# Combined_final.net
KiCad netlist of a schematic drawn in EAGLE
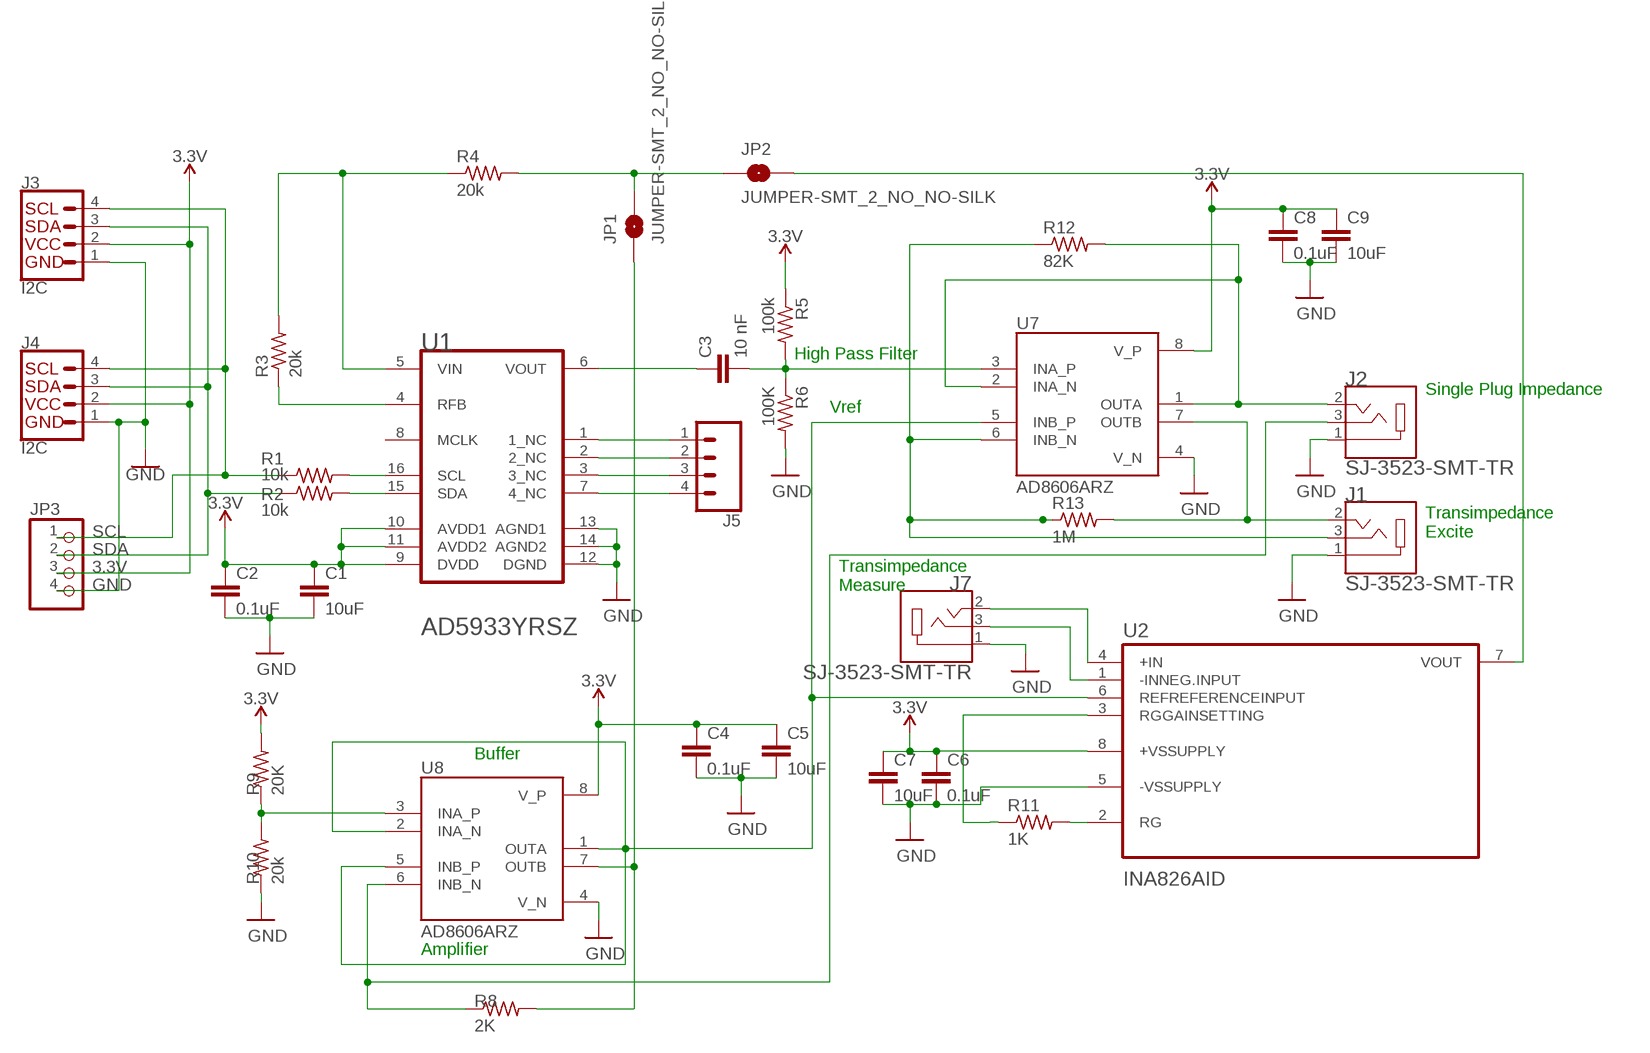
[diagram p0: schematic, sheet 1]

(export (version "E")
  (design (tool "Eeschema 10.0.6"))
  (components
    (comp (ref "C1")
      (value "10uF")
      (footprint "eagle-import:C0603")
      (libsource (lib "eagle-import") (part "C-EUC0603"))
    )
    (comp (ref "C2")
      (value "0.1uF")
      (footprint "eagle-import:C0603")
      (libsource (lib "eagle-import") (part "C-EUC0603"))
    )
    (comp (ref "C3")
      (value "10 nF")
      (footprint "eagle-import:C0603")
      (libsource (lib "eagle-import") (part "C-EUC0603"))
    )
    (comp (ref "C4")
      (value "0.1uF")
      (footprint "eagle-import:C0603")
      (libsource (lib "eagle-import") (part "C-EUC0603"))
    )
    (comp (ref "C5")
      (value "10uF")
      (footprint "eagle-import:C0603")
      (libsource (lib "eagle-import") (part "C-EUC0603"))
    )
    (comp (ref "C6")
      (value "0.1uF")
      (footprint "eagle-import:C0603")
      (libsource (lib "eagle-import") (part "C-EUC0603"))
    )
    (comp (ref "C7")
      (value "10uF")
      (footprint "eagle-import:C0603")
      (libsource (lib "eagle-import") (part "C-EUC0603"))
    )
    (comp (ref "C8")
      (value "0.1uF")
      (footprint "eagle-import:C0603")
      (libsource (lib "eagle-import") (part "C-EUC0603"))
    )
    (comp (ref "C9")
      (value "10uF")
      (footprint "eagle-import:C0603")
      (libsource (lib "eagle-import") (part "C-EUC0603"))
    )
    (comp (ref "J1")
      (value "SJ-3523-SMT-TR")
      (footprint "eagle-import:CUI_SJ-3523-SMT-TR")
      (fields (field (name "MF") "CUI Devices"))
      (libsource (lib "eagle-import") (part "SJ-3523-SMT-TR"))
    )
    (comp (ref "J2")
      (value "SJ-3523-SMT-TR")
      (footprint "eagle-import:CUI_SJ-3523-SMT-TR")
      (fields (field (name "MF") "CUI Devices"))
      (libsource (lib "eagle-import") (part "SJ-3523-SMT-TR"))
    )
    (comp (ref "J3")
      (value "I2C")
      (footprint "eagle-import:JST04_1MM_RA")
      (libsource (lib "eagle-import") (part "QWIIC_CONNECTORJS-1MM"))
    )
    (comp (ref "J4")
      (value "I2C")
      (footprint "eagle-import:JST04_1MM_RA")
      (libsource (lib "eagle-import") (part "QWIIC_CONNECTORJS-1MM"))
    )
    (comp (ref "J5")
      (value "CONN_04")
      (footprint "eagle-import:1X04")
      (libsource (lib "eagle-import") (part "CONN_04"))
    )
    (comp (ref "J7")
      (value "SJ-3523-SMT-TR")
      (footprint "eagle-import:CUI_SJ-3523-SMT-TR")
      (fields (field (name "MF") "CUI Devices"))
      (libsource (lib "eagle-import") (part "SJ-3523-SMT-TR"))
    )
    (comp (ref "JP1")
      (value "JUMPER-SMT_2_NO_NO-SILK")
      (footprint "eagle-import:SMT-JUMPER_2_NO_NO-SILK")
      (libsource (lib "eagle-import") (part "JUMPER-SMT_2_NO_NO-SILK"))
    )
    (comp (ref "JP2")
      (value "JUMPER-SMT_2_NO_NO-SILK")
      (footprint "eagle-import:SMT-JUMPER_2_NO_NO-SILK")
      (libsource (lib "eagle-import") (part "JUMPER-SMT_2_NO_NO-SILK"))
    )
    (comp (ref "JP3")
      (value "PINHD-1X4")
      (footprint "eagle-import:1X04")
      (libsource (lib "eagle-import") (part "PINHD-1X4"))
    )
    (comp (ref "R1")
      (value "10k")
      (footprint "eagle-import:R0603")
      (libsource (lib "eagle-import") (part "R-US_R0603"))
    )
    (comp (ref "R2")
      (value "10k")
      (footprint "eagle-import:R0603")
      (libsource (lib "eagle-import") (part "R-US_R0603"))
    )
    (comp (ref "R3")
      (value "20k")
      (footprint "eagle-import:R0603")
      (libsource (lib "eagle-import") (part "R-US_R0603"))
    )
    (comp (ref "R4")
      (value "20k")
      (footprint "eagle-import:R0603")
      (libsource (lib "eagle-import") (part "R-US_R0603"))
    )
    (comp (ref "R5")
      (value "100k")
      (footprint "eagle-import:R0603")
      (libsource (lib "eagle-import") (part "R-US_R0603"))
    )
    (comp (ref "R6")
      (value "100K")
      (footprint "eagle-import:R0603")
      (libsource (lib "eagle-import") (part "R-US_R0603"))
    )
    (comp (ref "R8")
      (value "2K")
      (footprint "eagle-import:R0603")
      (libsource (lib "eagle-import") (part "R-US_R0603"))
    )
    (comp (ref "R9")
      (value "20K")
      (footprint "eagle-import:R0603")
      (libsource (lib "eagle-import") (part "R-US_R0603"))
    )
    (comp (ref "R10")
      (value "20k")
      (footprint "eagle-import:R0603")
      (libsource (lib "eagle-import") (part "R-US_R0603"))
    )
    (comp (ref "R11")
      (value "1K")
      (footprint "eagle-import:R0603")
      (libsource (lib "eagle-import") (part "R-US_R0603"))
    )
    (comp (ref "R12")
      (value "82K")
      (footprint "eagle-import:R0603")
      (libsource (lib "eagle-import") (part "R-US_R0603"))
    )
    (comp (ref "R13")
      (value "1M")
      (footprint "eagle-import:R0603")
      (libsource (lib "eagle-import") (part "R-US_R0603"))
    )
    (comp (ref "U1")
      (value "ANALOG_DEVICES_AD5933YRSZANALOG_DEVICES_AD5933YRSZ_0_0")
      (footprint "eagle-import:ANALOG_DEVICES_AD5933YRSZ_0")
      (fields (field (name "MF") "Analog Devices") (field (name "MPN") "AD5933YRSZ"))
      (libsource (lib "eagle-import") (part "ANALOG_DEVICES_AD5933YRSZANALOG_DEVICES_AD5933YRSZ_0_0"))
    )
    (comp (ref "U2")
      (value "INA826AID")
      (footprint "eagle-import:SOIC127P599X175-8N")
      (fields (field (name "MF") "Texas Instruments"))
      (libsource (lib "eagle-import") (part "INA826AID"))
    )
    (comp (ref "U7")
      (value "AD8606ARZ")
      (footprint "eagle-import:SOIC127P600X175-8N")
      (fields (field (name "MF") "Analog Devices"))
      (libsource (lib "eagle-import") (part "AD8606ARZ"))
    )
    (comp (ref "U8")
      (value "AD8606ARZ")
      (footprint "eagle-import:SOIC127P600X175-8N")
      (fields (field (name "MF") "Analog Devices"))
      (libsource (lib "eagle-import") (part "AD8606ARZ"))
    )
  )
  (nets
    (net (code "1") (name "/SCL") (class "Default")
      (node (ref "J3") (pin "4") (pinfunction "4_4") (pintype "passive"))
      (node (ref "J4") (pin "4") (pinfunction "4_4") (pintype "passive"))
      (node (ref "JP3") (pin "1") (pinfunction "1_1") (pintype "passive"))
      (node (ref "R1") (pin "1") (pinfunction "1_1") (pintype "passive"))
    )
    (net (code "2") (name "/SDA") (class "Default")
      (node (ref "J3") (pin "3") (pinfunction "3_3") (pintype "passive"))
      (node (ref "J4") (pin "3") (pinfunction "3_3") (pintype "passive"))
      (node (ref "JP3") (pin "2") (pinfunction "2_2") (pintype "passive"))
      (node (ref "R2") (pin "1") (pinfunction "1_1") (pintype "passive"))
    )
    (net (code "3") (name "3.3V") (class "Default")
      (node (ref "C1") (pin "1") (pinfunction "1_1") (pintype "passive"))
      (node (ref "C2") (pin "1") (pinfunction "1_1") (pintype "passive"))
      (node (ref "C4") (pin "1") (pinfunction "1_1") (pintype "passive"))
      (node (ref "C5") (pin "1") (pinfunction "1_1") (pintype "passive"))
      (node (ref "C6") (pin "1") (pinfunction "1_1") (pintype "passive"))
      (node (ref "C7") (pin "1") (pinfunction "1_1") (pintype "passive"))
      (node (ref "C8") (pin "1") (pinfunction "1_1") (pintype "passive"))
      (node (ref "C9") (pin "1") (pinfunction "1_1") (pintype "passive"))
      (node (ref "J3") (pin "2") (pinfunction "2_2") (pintype "power_in"))
      (node (ref "J4") (pin "2") (pinfunction "2_2") (pintype "power_in"))
      (node (ref "JP3") (pin "3") (pinfunction "3_3") (pintype "passive"))
      (node (ref "R5") (pin "1") (pinfunction "1_1") (pintype "passive"))
      (node (ref "R9") (pin "2") (pinfunction "2_2") (pintype "passive"))
      (node (ref "U1") (pin "10") (pinfunction "AVDD1_10") (pintype "power_in"))
      (node (ref "U1") (pin "11") (pinfunction "AVDD2_11") (pintype "power_in"))
      (node (ref "U1") (pin "9") (pinfunction "DVDD_9") (pintype "power_in"))
      (node (ref "U2") (pin "8") (pinfunction "+VSSUPPLY_8") (pintype "bidirectional"))
      (node (ref "U7") (pin "8") (pinfunction "V_P_8") (pintype "power_in"))
      (node (ref "U8") (pin "8") (pinfunction "V_P_8") (pintype "power_in"))
    )
    (net (code "4") (name "GND") (class "Default")
      (node (ref "C1") (pin "2") (pinfunction "2_2") (pintype "passive"))
      (node (ref "C2") (pin "2") (pinfunction "2_2") (pintype "passive"))
      (node (ref "C4") (pin "2") (pinfunction "2_2") (pintype "passive"))
      (node (ref "C5") (pin "2") (pinfunction "2_2") (pintype "passive"))
      (node (ref "C6") (pin "2") (pinfunction "2_2") (pintype "passive"))
      (node (ref "C7") (pin "2") (pinfunction "2_2") (pintype "passive"))
      (node (ref "C8") (pin "2") (pinfunction "2_2") (pintype "passive"))
      (node (ref "C9") (pin "2") (pinfunction "2_2") (pintype "passive"))
      (node (ref "J1") (pin "1") (pinfunction "1_1") (pintype "passive"))
      (node (ref "J2") (pin "1") (pinfunction "1_1") (pintype "passive"))
      (node (ref "J3") (pin "1") (pinfunction "1_1") (pintype "power_in"))
      (node (ref "J4") (pin "1") (pinfunction "1_1") (pintype "power_in"))
      (node (ref "J7") (pin "1") (pinfunction "1_1") (pintype "passive"))
      (node (ref "JP3") (pin "4") (pinfunction "4_4") (pintype "passive"))
      (node (ref "R10") (pin "1") (pinfunction "1_1") (pintype "passive"))
      (node (ref "R6") (pin "2") (pinfunction "2_2") (pintype "passive"))
      (node (ref "U1") (pin "12") (pinfunction "DGND_12") (pintype "power_in"))
      (node (ref "U1") (pin "13") (pinfunction "AGND1_13") (pintype "power_in"))
      (node (ref "U1") (pin "14") (pinfunction "AGND2_14") (pintype "power_in"))
      (node (ref "U2") (pin "5") (pinfunction "-VSSUPPLY_5") (pintype "bidirectional"))
      (node (ref "U7") (pin "4") (pinfunction "V_N_4") (pintype "power_in"))
      (node (ref "U8") (pin "4") (pinfunction "V_N_4") (pintype "power_in"))
    )
    (net (code "5") (name "Net-(JP1-Pad2)") (class "Default")
      (node (ref "JP1") (pin "2") (pinfunction "2_2") (pintype "passive"))
      (node (ref "JP2") (pin "1") (pinfunction "1_1") (pintype "passive"))
      (node (ref "R4") (pin "2") (pinfunction "2_2") (pintype "passive"))
    )
    (net (code "6") (name "Net-(U1-1_NC)") (class "Default")
      (node (ref "J5") (pin "1") (pinfunction "1_1") (pintype "passive"))
      (node (ref "U1") (pin "1") (pinfunction "1_NC_1") (pintype "passive"))
    )
    (net (code "7") (name "Net-(U1-2_NC)") (class "Default")
      (node (ref "J5") (pin "2") (pinfunction "2_2") (pintype "passive"))
      (node (ref "U1") (pin "2") (pinfunction "2_NC_2") (pintype "passive"))
    )
    (net (code "8") (name "Net-(U1-3_NC)") (class "Default")
      (node (ref "J5") (pin "3") (pinfunction "3_3") (pintype "passive"))
      (node (ref "U1") (pin "3") (pinfunction "3_NC_3") (pintype "passive"))
    )
    (net (code "9") (name "Net-(U1-4_NC)") (class "Default")
      (node (ref "J5") (pin "4") (pinfunction "4_4") (pintype "passive"))
      (node (ref "U1") (pin "7") (pinfunction "4_NC_7") (pintype "passive"))
    )
    (net (code "10") (name "Net-(U1-RFB)") (class "Default")
      (node (ref "R3") (pin "1") (pinfunction "1_1") (pintype "passive"))
      (node (ref "U1") (pin "4") (pinfunction "RFB_4") (pintype "input"))
    )
    (net (code "11") (name "Net-(U1-SCL)") (class "Default")
      (node (ref "R1") (pin "2") (pinfunction "2_2") (pintype "passive"))
      (node (ref "U1") (pin "16") (pinfunction "SCL_16") (pintype "input"))
    )
    (net (code "12") (name "Net-(U1-SDA)") (class "Default")
      (node (ref "R2") (pin "2") (pinfunction "2_2") (pintype "passive"))
      (node (ref "U1") (pin "15") (pinfunction "SDA_15") (pintype "bidirectional"))
    )
    (net (code "13") (name "Net-(U1-VIN)") (class "Default")
      (node (ref "R3") (pin "2") (pinfunction "2_2") (pintype "passive"))
      (node (ref "R4") (pin "1") (pinfunction "1_1") (pintype "passive"))
      (node (ref "U1") (pin "5") (pinfunction "VIN_5") (pintype "input"))
    )
    (net (code "14") (name "Net-(U1-VOUT)") (class "Default")
      (node (ref "C3") (pin "1") (pinfunction "1_1") (pintype "passive"))
      (node (ref "U1") (pin "6") (pinfunction "VOUT_6") (pintype "output"))
    )
    (net (code "15") (name "Net-(U2-+IN)") (class "Default")
      (node (ref "J7") (pin "2") (pinfunction "2_2") (pintype "passive"))
      (node (ref "U2") (pin "4") (pinfunction "+IN_4") (pintype "input"))
    )
    (net (code "16") (name "Net-(U2--INNEG.INPUT)") (class "Default")
      (node (ref "J7") (pin "3") (pinfunction "3_3") (pintype "passive"))
      (node (ref "U2") (pin "1") (pinfunction "-INNEG.INPUT_1") (pintype "input"))
    )
    (net (code "17") (name "Net-(U2-REFREFERENCEINPUT)") (class "Default")
      (node (ref "U2") (pin "6") (pinfunction "REFREFERENCEINPUT_6") (pintype "input"))
      (node (ref "U7") (pin "5") (pinfunction "INB_P_5") (pintype "input"))
      (node (ref "U8") (pin "1") (pinfunction "OUTA_1") (pintype "input"))
      (node (ref "U8") (pin "2") (pinfunction "INA_N_2") (pintype "input"))
      (node (ref "U8") (pin "5") (pinfunction "INB_P_5") (pintype "input"))
    )
    (net (code "18") (name "Net-(U2-RG)") (class "Default")
      (node (ref "R11") (pin "2") (pinfunction "2_2") (pintype "passive"))
      (node (ref "U2") (pin "2") (pinfunction "RG_2") (pintype "bidirectional"))
    )
    (net (code "19") (name "Net-(U2-RGGAINSETTING)") (class "Default")
      (node (ref "R11") (pin "1") (pinfunction "1_1") (pintype "passive"))
      (node (ref "U2") (pin "3") (pinfunction "RGGAINSETTING_3") (pintype "input"))
    )
    (net (code "20") (name "Net-(U2-VOUT)") (class "Default")
      (node (ref "JP2") (pin "2") (pinfunction "2_2") (pintype "passive"))
      (node (ref "U2") (pin "7") (pinfunction "VOUT_7") (pintype "output"))
    )
    (net (code "21") (name "Net-(U7-INA_N)") (class "Default")
      (node (ref "J2") (pin "2") (pinfunction "2_2") (pintype "passive"))
      (node (ref "R12") (pin "2") (pinfunction "2_2") (pintype "passive"))
      (node (ref "U7") (pin "1") (pinfunction "OUTA_1") (pintype "input"))
      (node (ref "U7") (pin "2") (pinfunction "INA_N_2") (pintype "input"))
    )
    (net (code "22") (name "Net-(U7-INA_P)") (class "Default")
      (node (ref "C3") (pin "2") (pinfunction "2_2") (pintype "passive"))
      (node (ref "R5") (pin "2") (pinfunction "2_2") (pintype "passive"))
      (node (ref "R6") (pin "1") (pinfunction "1_1") (pintype "passive"))
      (node (ref "U7") (pin "3") (pinfunction "INA_P_3") (pintype "input"))
    )
    (net (code "23") (name "Net-(U7-INB_N)") (class "Default")
      (node (ref "J1") (pin "3") (pinfunction "3_3") (pintype "passive"))
      (node (ref "R12") (pin "1") (pinfunction "1_1") (pintype "passive"))
      (node (ref "R13") (pin "1") (pinfunction "1_1") (pintype "passive"))
      (node (ref "U7") (pin "6") (pinfunction "INB_N_6") (pintype "input"))
    )
    (net (code "24") (name "Net-(U7-OUTB)") (class "Default")
      (node (ref "J1") (pin "2") (pinfunction "2_2") (pintype "passive"))
      (node (ref "R13") (pin "2") (pinfunction "2_2") (pintype "passive"))
      (node (ref "U7") (pin "7") (pinfunction "OUTB_7") (pintype "input"))
    )
    (net (code "25") (name "Net-(U8-INA_P)") (class "Default")
      (node (ref "R10") (pin "2") (pinfunction "2_2") (pintype "passive"))
      (node (ref "R9") (pin "1") (pinfunction "1_1") (pintype "passive"))
      (node (ref "U8") (pin "3") (pinfunction "INA_P_3") (pintype "input"))
    )
    (net (code "26") (name "Net-(U8-INB_N)") (class "Default")
      (node (ref "J2") (pin "3") (pinfunction "3_3") (pintype "passive"))
      (node (ref "R8") (pin "1") (pinfunction "1_1") (pintype "passive"))
      (node (ref "U8") (pin "6") (pinfunction "INB_N_6") (pintype "input"))
    )
    (net (code "27") (name "Net-(U8-OUTB)") (class "Default")
      (node (ref "JP1") (pin "1") (pinfunction "1_1") (pintype "passive"))
      (node (ref "R8") (pin "2") (pinfunction "2_2") (pintype "passive"))
      (node (ref "U8") (pin "7") (pinfunction "OUTB_7") (pintype "input"))
    )
    (net (code "28") (name "unconnected-(U1-MCLK-Pad8)") (class "Default")
      (node (ref "U1") (pin "8") (pinfunction "MCLK_8") (pintype "input"))
    )
  )
)
